# MeasurementCircuit.net
KiCad netlist of a schematic drawn in Altium Designer
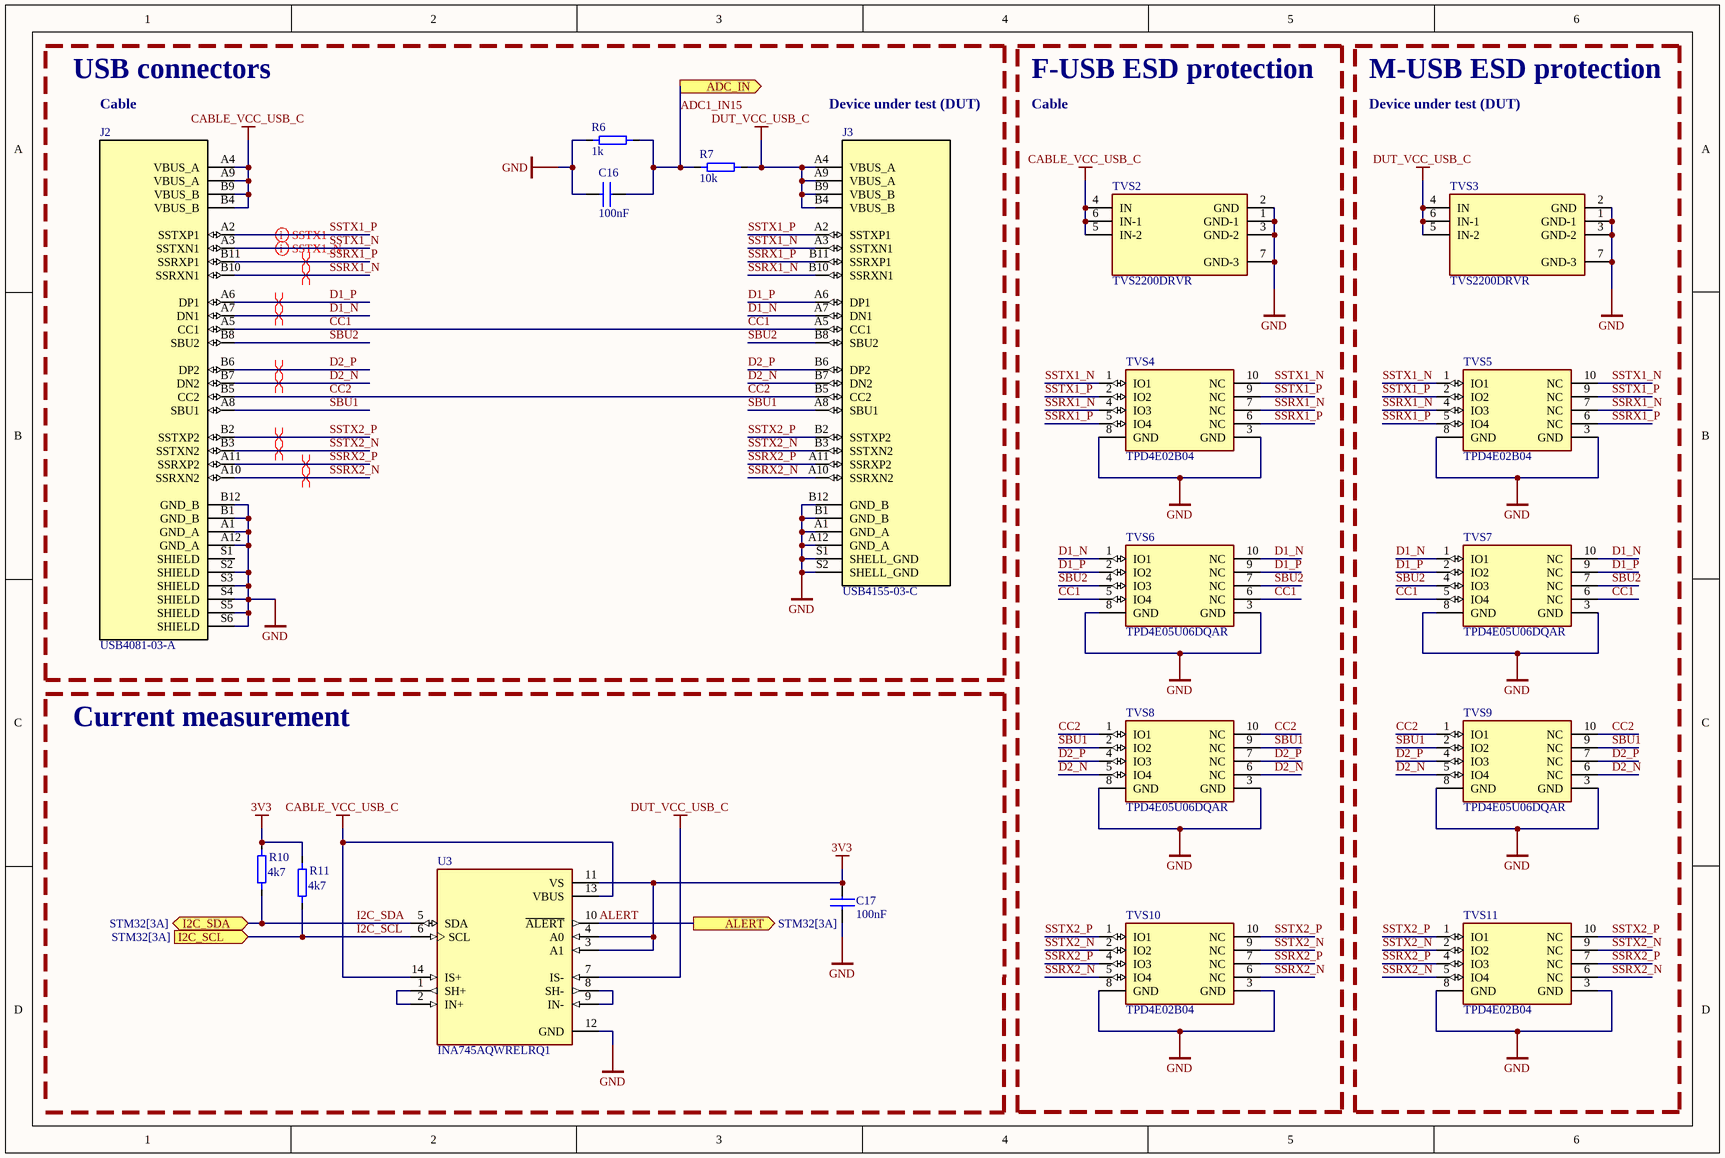
[diagram p0: MeasurementCircuit.SchDoc]

(export (version "E")
  (design (tool "Eeschema 10.0.6"))
  (components
    (comp (ref "C16")
      (value "100nF")
      (footprint "C0402")
      (description "Kondensator ceramiczny SMD")
      (libsource (lib "n16_discrete") (part "C"))
    )
    (comp (ref "C17")
      (value "100nF")
      (footprint "C0402")
      (description "Kondensator ceramiczny SMD")
      (libsource (lib "n16_discrete") (part "C"))
    )
    (comp (ref "J2")
      (value "USB4081-03-A")
      (footprint "USB4081-03-A")
      (description "Type C USB 3.2 Gen 2 Connector")
      (libsource (lib "USB_connectors") (part "USB4081-03-A"))
    )
    (comp (ref "J3")
      (value "USB4155-03-C")
      (footprint "USB4155-03-C")
      (libsource (lib "USB_connectors") (part "USB4155-03-C"))
    )
    (comp (ref "R6")
      (value "1k")
      (footprint "R0402")
      (description "Rezystor SMD")
      (libsource (lib "n16_discrete") (part "R"))
    )
    (comp (ref "R7")
      (value "10k")
      (footprint "R0603")
      (description "Rezystor SMD")
      (libsource (lib "n16_discrete") (part "R"))
    )
    (comp (ref "R10")
      (value "4k7")
      (footprint "R0402")
      (description "Rezystor SMD")
      (libsource (lib "n16_discrete") (part "R"))
    )
    (comp (ref "R11")
      (value "4k7")
      (footprint "R0402")
      (description "Rezystor SMD")
      (libsource (lib "n16_discrete") (part "R"))
    )
    (comp (ref "TVS2")
      (value "TVS2200DRVR")
      (footprint "TVS2200DRVR")
      (description "22V flat-clamp surge protection device")
      (libsource (lib "ESD_Protection") (part "TVS2200DRVR"))
    )
    (comp (ref "TVS3")
      (value "TVS2200DRVR")
      (footprint "TVS2200DRVR")
      (description "22V flat-clamp surge protection device")
      (libsource (lib "ESD_Protection") (part "TVS2200DRVR"))
    )
    (comp (ref "TVS4")
      (value "TPD4E02B04")
      (footprint "TPD4E02B04")
      (libsource (lib "ESD_Protection") (part "TPD4E02B04"))
    )
    (comp (ref "TVS5")
      (value "TPD4E02B04")
      (footprint "TPD4E02B04")
      (libsource (lib "ESD_Protection") (part "TPD4E02B04"))
    )
    (comp (ref "TVS6")
      (value "TPD4E05U06DQAR")
      (footprint "TPD4E05U06DQAR")
      (description "ESD Protection Diodes / TVS Diodes 0.66-pF +/-3.6-V +/- 30-kV ESD protectio")
      (libsource (lib "ESD_Protection") (part "TPD4E05U06DQAR"))
    )
    (comp (ref "TVS7")
      (value "TPD4E05U06DQAR")
      (footprint "TPD4E05U06DQAR")
      (description "ESD Protection Diodes / TVS Diodes 0.66-pF +/-3.6-V +/- 30-kV ESD protectio")
      (libsource (lib "ESD_Protection") (part "TPD4E05U06DQAR"))
    )
    (comp (ref "TVS8")
      (value "TPD4E05U06DQAR")
      (footprint "TPD4E05U06DQAR")
      (description "ESD Protection Diodes / TVS Diodes 0.66-pF +/-3.6-V +/- 30-kV ESD protectio")
      (libsource (lib "ESD_Protection") (part "TPD4E05U06DQAR"))
    )
    (comp (ref "TVS9")
      (value "TPD4E05U06DQAR")
      (footprint "TPD4E05U06DQAR")
      (description "ESD Protection Diodes / TVS Diodes 0.66-pF +/-3.6-V +/- 30-kV ESD protectio")
      (libsource (lib "ESD_Protection") (part "TPD4E05U06DQAR"))
    )
    (comp (ref "TVS10")
      (value "TPD4E02B04")
      (footprint "TPD4E02B04")
      (libsource (lib "ESD_Protection") (part "TPD4E02B04"))
    )
    (comp (ref "TVS11")
      (value "TPD4E02B04")
      (footprint "TPD4E02B04")
      (libsource (lib "ESD_Protection") (part "TPD4E02B04"))
    )
    (comp (ref "U3")
      (value "INA745AQWRELRQ1")
      (footprint "INA745AQWRELRQ1")
      (libsource (lib "ICs") (part "INA745AQWRELRQ1"))
    )
  )
  (nets
    (net (code "1") (name "/ADC1_IN15") (class "Default")
      (node (ref "C16") (pin "1") (pinfunction "1_1") (pintype "passive"))
      (node (ref "R6") (pin "2") (pinfunction "2_2") (pintype "passive"))
      (node (ref "R7") (pin "1") (pinfunction "1_1") (pintype "passive"))
    )
    (net (code "2") (name "/ALERT") (class "Default")
      (node (ref "U3") (pin "10") (pinfunction "~{ALERT}_10") (pintype "output"))
    )
    (net (code "3") (name "/CC1") (class "Default")
      (node (ref "J2") (pin "A5") (pinfunction "CC1_A5") (pintype "bidirectional"))
      (node (ref "J3") (pin "A5") (pinfunction "CC1_A5") (pintype "bidirectional"))
      (node (ref "TVS6") (pin "5") (pinfunction "IO4_5") (pintype "bidirectional"))
      (node (ref "TVS6") (pin "6") (pinfunction "NC_6") (pintype "passive"))
      (node (ref "TVS7") (pin "5") (pinfunction "IO4_5") (pintype "bidirectional"))
      (node (ref "TVS7") (pin "6") (pinfunction "NC_6") (pintype "passive"))
    )
    (net (code "4") (name "/CC2") (class "Default")
      (node (ref "J2") (pin "B5") (pinfunction "CC2_B5") (pintype "bidirectional"))
      (node (ref "J3") (pin "B5") (pinfunction "CC2_B5") (pintype "bidirectional"))
      (node (ref "TVS8") (pin "1") (pinfunction "IO1_1") (pintype "bidirectional"))
      (node (ref "TVS8") (pin "10") (pinfunction "NC_10") (pintype "passive"))
      (node (ref "TVS9") (pin "1") (pinfunction "IO1_1") (pintype "bidirectional"))
      (node (ref "TVS9") (pin "10") (pinfunction "NC_10") (pintype "passive"))
    )
    (net (code "5") (name "/D1_N") (class "Default")
      (node (ref "J2") (pin "A7") (pinfunction "DN1_A7") (pintype "bidirectional"))
      (node (ref "J3") (pin "A7") (pinfunction "DN1_A7") (pintype "bidirectional"))
      (node (ref "TVS6") (pin "1") (pinfunction "IO1_1") (pintype "bidirectional"))
      (node (ref "TVS6") (pin "10") (pinfunction "NC_10") (pintype "passive"))
      (node (ref "TVS7") (pin "1") (pinfunction "IO1_1") (pintype "bidirectional"))
      (node (ref "TVS7") (pin "10") (pinfunction "NC_10") (pintype "passive"))
    )
    (net (code "6") (name "/D1_P") (class "Default")
      (node (ref "J2") (pin "A6") (pinfunction "DP1_A6") (pintype "bidirectional"))
      (node (ref "J3") (pin "A6") (pinfunction "DP1_A6") (pintype "bidirectional"))
      (node (ref "TVS6") (pin "2") (pinfunction "IO2_2") (pintype "bidirectional"))
      (node (ref "TVS6") (pin "9") (pinfunction "NC_9") (pintype "passive"))
      (node (ref "TVS7") (pin "2") (pinfunction "IO2_2") (pintype "bidirectional"))
      (node (ref "TVS7") (pin "9") (pinfunction "NC_9") (pintype "passive"))
    )
    (net (code "7") (name "/D2_N") (class "Default")
      (node (ref "J2") (pin "B7") (pinfunction "DN2_B7") (pintype "bidirectional"))
      (node (ref "J3") (pin "B7") (pinfunction "DN2_B7") (pintype "bidirectional"))
      (node (ref "TVS8") (pin "5") (pinfunction "IO4_5") (pintype "bidirectional"))
      (node (ref "TVS8") (pin "6") (pinfunction "NC_6") (pintype "passive"))
      (node (ref "TVS9") (pin "5") (pinfunction "IO4_5") (pintype "bidirectional"))
      (node (ref "TVS9") (pin "6") (pinfunction "NC_6") (pintype "passive"))
    )
    (net (code "8") (name "/D2_P") (class "Default")
      (node (ref "J2") (pin "B6") (pinfunction "DP2_B6") (pintype "bidirectional"))
      (node (ref "J3") (pin "B6") (pinfunction "DP2_B6") (pintype "bidirectional"))
      (node (ref "TVS8") (pin "4") (pinfunction "IO3_4") (pintype "bidirectional"))
      (node (ref "TVS8") (pin "7") (pinfunction "NC_7") (pintype "passive"))
      (node (ref "TVS9") (pin "4") (pinfunction "IO3_4") (pintype "bidirectional"))
      (node (ref "TVS9") (pin "7") (pinfunction "NC_7") (pintype "passive"))
    )
    (net (code "9") (name "/I2C_SCL") (class "Default")
      (node (ref "R11") (pin "2") (pinfunction "2_2") (pintype "passive"))
      (node (ref "U3") (pin "6") (pinfunction "SCL_6") (pintype "input"))
    )
    (net (code "10") (name "/I2C_SDA") (class "Default")
      (node (ref "R10") (pin "2") (pinfunction "2_2") (pintype "passive"))
      (node (ref "U3") (pin "5") (pinfunction "SDA_5") (pintype "bidirectional"))
    )
    (net (code "11") (name "/SBU1") (class "Default")
      (node (ref "J2") (pin "A8") (pinfunction "SBU1_A8") (pintype "bidirectional"))
      (node (ref "J3") (pin "A8") (pinfunction "SBU1_A8") (pintype "bidirectional"))
      (node (ref "TVS8") (pin "2") (pinfunction "IO2_2") (pintype "bidirectional"))
      (node (ref "TVS8") (pin "9") (pinfunction "NC_9") (pintype "passive"))
      (node (ref "TVS9") (pin "2") (pinfunction "IO2_2") (pintype "bidirectional"))
      (node (ref "TVS9") (pin "9") (pinfunction "NC_9") (pintype "passive"))
    )
    (net (code "12") (name "/SBU2") (class "Default")
      (node (ref "J2") (pin "B8") (pinfunction "SBU2_B8") (pintype "bidirectional"))
      (node (ref "J3") (pin "B8") (pinfunction "SBU2_B8") (pintype "bidirectional"))
      (node (ref "TVS6") (pin "4") (pinfunction "IO3_4") (pintype "bidirectional"))
      (node (ref "TVS6") (pin "7") (pinfunction "NC_7") (pintype "passive"))
      (node (ref "TVS7") (pin "4") (pinfunction "IO3_4") (pintype "bidirectional"))
      (node (ref "TVS7") (pin "7") (pinfunction "NC_7") (pintype "passive"))
    )
    (net (code "13") (name "/SSRX1_N") (class "Default")
      (node (ref "J2") (pin "B10") (pinfunction "SSRXN1_B10") (pintype "bidirectional"))
      (node (ref "J3") (pin "B10") (pinfunction "SSRXN1_B10") (pintype "bidirectional"))
      (node (ref "TVS4") (pin "4") (pinfunction "IO3_4") (pintype "bidirectional"))
      (node (ref "TVS4") (pin "7") (pinfunction "NC_7") (pintype "passive"))
      (node (ref "TVS5") (pin "4") (pinfunction "IO3_4") (pintype "bidirectional"))
      (node (ref "TVS5") (pin "7") (pinfunction "NC_7") (pintype "passive"))
    )
    (net (code "14") (name "/SSRX1_P") (class "Default")
      (node (ref "J2") (pin "B11") (pinfunction "SSRXP1_B11") (pintype "bidirectional"))
      (node (ref "J3") (pin "B11") (pinfunction "SSRXP1_B11") (pintype "bidirectional"))
      (node (ref "TVS4") (pin "5") (pinfunction "IO4_5") (pintype "bidirectional"))
      (node (ref "TVS4") (pin "6") (pinfunction "NC_6") (pintype "passive"))
      (node (ref "TVS5") (pin "5") (pinfunction "IO4_5") (pintype "bidirectional"))
      (node (ref "TVS5") (pin "6") (pinfunction "NC_6") (pintype "passive"))
    )
    (net (code "15") (name "/SSRX2_N") (class "Default")
      (node (ref "J2") (pin "A10") (pinfunction "SSRXN2_A10") (pintype "bidirectional"))
      (node (ref "J3") (pin "A10") (pinfunction "SSRXN2_A10") (pintype "bidirectional"))
      (node (ref "TVS10") (pin "5") (pinfunction "IO4_5") (pintype "bidirectional"))
      (node (ref "TVS10") (pin "6") (pinfunction "NC_6") (pintype "passive"))
      (node (ref "TVS11") (pin "5") (pinfunction "IO4_5") (pintype "bidirectional"))
      (node (ref "TVS11") (pin "6") (pinfunction "NC_6") (pintype "passive"))
    )
    (net (code "16") (name "/SSRX2_P") (class "Default")
      (node (ref "J2") (pin "A11") (pinfunction "SSRXP2_A11") (pintype "bidirectional"))
      (node (ref "J3") (pin "A11") (pinfunction "SSRXP2_A11") (pintype "bidirectional"))
      (node (ref "TVS10") (pin "4") (pinfunction "IO3_4") (pintype "bidirectional"))
      (node (ref "TVS10") (pin "7") (pinfunction "NC_7") (pintype "passive"))
      (node (ref "TVS11") (pin "4") (pinfunction "IO3_4") (pintype "bidirectional"))
      (node (ref "TVS11") (pin "7") (pinfunction "NC_7") (pintype "passive"))
    )
    (net (code "17") (name "/SSTX1_N") (class "Default")
      (node (ref "J2") (pin "A3") (pinfunction "SSTXN1_A3") (pintype "bidirectional"))
      (node (ref "J3") (pin "A3") (pinfunction "SSTXN1_A3") (pintype "bidirectional"))
      (node (ref "TVS4") (pin "1") (pinfunction "IO1_1") (pintype "bidirectional"))
      (node (ref "TVS4") (pin "10") (pinfunction "NC_10") (pintype "passive"))
      (node (ref "TVS5") (pin "1") (pinfunction "IO1_1") (pintype "bidirectional"))
      (node (ref "TVS5") (pin "10") (pinfunction "NC_10") (pintype "passive"))
    )
    (net (code "18") (name "/SSTX1_P") (class "Default")
      (node (ref "J2") (pin "A2") (pinfunction "SSTXP1_A2") (pintype "bidirectional"))
      (node (ref "J3") (pin "A2") (pinfunction "SSTXP1_A2") (pintype "bidirectional"))
      (node (ref "TVS4") (pin "2") (pinfunction "IO2_2") (pintype "bidirectional"))
      (node (ref "TVS4") (pin "9") (pinfunction "NC_9") (pintype "passive"))
      (node (ref "TVS5") (pin "2") (pinfunction "IO2_2") (pintype "bidirectional"))
      (node (ref "TVS5") (pin "9") (pinfunction "NC_9") (pintype "passive"))
    )
    (net (code "19") (name "/SSTX2_N") (class "Default")
      (node (ref "J2") (pin "B3") (pinfunction "SSTXN2_B3") (pintype "bidirectional"))
      (node (ref "J3") (pin "B3") (pinfunction "SSTXN2_B3") (pintype "bidirectional"))
      (node (ref "TVS10") (pin "2") (pinfunction "IO2_2") (pintype "bidirectional"))
      (node (ref "TVS10") (pin "9") (pinfunction "NC_9") (pintype "passive"))
      (node (ref "TVS11") (pin "2") (pinfunction "IO2_2") (pintype "bidirectional"))
      (node (ref "TVS11") (pin "9") (pinfunction "NC_9") (pintype "passive"))
    )
    (net (code "20") (name "/SSTX2_P") (class "Default")
      (node (ref "J2") (pin "B2") (pinfunction "SSTXP2_B2") (pintype "bidirectional"))
      (node (ref "J3") (pin "B2") (pinfunction "SSTXP2_B2") (pintype "bidirectional"))
      (node (ref "TVS10") (pin "1") (pinfunction "IO1_1") (pintype "bidirectional"))
      (node (ref "TVS10") (pin "10") (pinfunction "NC_10") (pintype "passive"))
      (node (ref "TVS11") (pin "1") (pinfunction "IO1_1") (pintype "bidirectional"))
      (node (ref "TVS11") (pin "10") (pinfunction "NC_10") (pintype "passive"))
    )
    (net (code "21") (name "3V3") (class "Default")
      (node (ref "C17") (pin "1") (pinfunction "1_1") (pintype "passive"))
      (node (ref "R10") (pin "1") (pinfunction "1_1") (pintype "passive"))
      (node (ref "R11") (pin "1") (pinfunction "1_1") (pintype "passive"))
      (node (ref "U3") (pin "11") (pinfunction "VS_11") (pintype "power_in"))
      (node (ref "U3") (pin "3") (pinfunction "A1_3") (pintype "input"))
      (node (ref "U3") (pin "4") (pinfunction "A0_4") (pintype "input"))
    )
    (net (code "22") (name "CABLE_VCC_USB_C") (class "Default")
      (node (ref "J2") (pin "A4") (pinfunction "VBUS_A_A4") (pintype "power_in"))
      (node (ref "J2") (pin "A9") (pinfunction "VBUS_A_A9") (pintype "power_in"))
      (node (ref "J2") (pin "B4") (pinfunction "VBUS_B_B4") (pintype "power_in"))
      (node (ref "J2") (pin "B9") (pinfunction "VBUS_B_B9") (pintype "power_in"))
      (node (ref "TVS2") (pin "4") (pinfunction "IN_4") (pintype "power_in"))
      (node (ref "TVS2") (pin "5") (pinfunction "IN-2_5") (pintype "power_in"))
      (node (ref "TVS2") (pin "6") (pinfunction "IN-1_6") (pintype "power_in"))
      (node (ref "U3") (pin "13") (pinfunction "VBUS_13") (pintype "power_in"))
      (node (ref "U3") (pin "14") (pinfunction "IS+_14") (pintype "input"))
    )
    (net (code "23") (name "DUT_VCC_USB_C") (class "Default")
      (node (ref "J3") (pin "A4") (pinfunction "VBUS_A_A4") (pintype "power_in"))
      (node (ref "J3") (pin "A9") (pinfunction "VBUS_A_A9") (pintype "power_in"))
      (node (ref "J3") (pin "B4") (pinfunction "VBUS_B_B4") (pintype "power_in"))
      (node (ref "J3") (pin "B9") (pinfunction "VBUS_B_B9") (pintype "power_in"))
      (node (ref "R7") (pin "2") (pinfunction "2_2") (pintype "passive"))
      (node (ref "TVS3") (pin "4") (pinfunction "IN_4") (pintype "power_in"))
      (node (ref "TVS3") (pin "5") (pinfunction "IN-2_5") (pintype "power_in"))
      (node (ref "TVS3") (pin "6") (pinfunction "IN-1_6") (pintype "power_in"))
      (node (ref "U3") (pin "7") (pinfunction "IS-_7") (pintype "input"))
    )
    (net (code "24") (name "GND") (class "Default")
      (node (ref "C16") (pin "2") (pinfunction "2_2") (pintype "passive"))
      (node (ref "C17") (pin "2") (pinfunction "2_2") (pintype "passive"))
      (node (ref "J2") (pin "A1") (pinfunction "GND_A_A1") (pintype "power_in"))
      (node (ref "J2") (pin "A12") (pinfunction "GND_A_A12") (pintype "power_in"))
      (node (ref "J2") (pin "B1") (pinfunction "GND_B_B1") (pintype "power_in"))
      (node (ref "J2") (pin "B12") (pinfunction "GND_B_B12") (pintype "power_in"))
      (node (ref "J2") (pin "S2") (pinfunction "SHIELD_S2") (pintype "power_in"))
      (node (ref "J2") (pin "S3") (pinfunction "SHIELD_S3") (pintype "passive"))
      (node (ref "J2") (pin "S4") (pinfunction "SHIELD_S4") (pintype "passive"))
      (node (ref "J2") (pin "S5") (pinfunction "SHIELD_S5") (pintype "passive"))
      (node (ref "J2") (pin "S6") (pinfunction "SHIELD_S6") (pintype "passive"))
      (node (ref "J3") (pin "A1") (pinfunction "GND_A_A1") (pintype "power_in"))
      (node (ref "J3") (pin "A12") (pinfunction "GND_A_A12") (pintype "power_in"))
      (node (ref "J3") (pin "B1") (pinfunction "GND_B_B1") (pintype "power_in"))
      (node (ref "J3") (pin "B12") (pinfunction "GND_B_B12") (pintype "power_in"))
      (node (ref "J3") (pin "S1") (pinfunction "SHELL_GND_S1") (pintype "power_in"))
      (node (ref "J3") (pin "S2") (pinfunction "SHELL_GND_S2") (pintype "power_in"))
      (node (ref "R6") (pin "1") (pinfunction "1_1") (pintype "passive"))
      (node (ref "TVS10") (pin "3") (pinfunction "GND_3") (pintype "power_in"))
      (node (ref "TVS10") (pin "8") (pinfunction "GND_8") (pintype "power_in"))
      (node (ref "TVS11") (pin "3") (pinfunction "GND_3") (pintype "power_in"))
      (node (ref "TVS11") (pin "8") (pinfunction "GND_8") (pintype "power_in"))
      (node (ref "TVS2") (pin "1") (pinfunction "GND-1_1") (pintype "power_in"))
      (node (ref "TVS2") (pin "2") (pinfunction "GND_2") (pintype "power_in"))
      (node (ref "TVS2") (pin "3") (pinfunction "GND-2_3") (pintype "power_in"))
      (node (ref "TVS2") (pin "7") (pinfunction "GND-3_7") (pintype "power_in"))
      (node (ref "TVS3") (pin "1") (pinfunction "GND-1_1") (pintype "power_in"))
      (node (ref "TVS3") (pin "2") (pinfunction "GND_2") (pintype "power_in"))
      (node (ref "TVS3") (pin "3") (pinfunction "GND-2_3") (pintype "power_in"))
      (node (ref "TVS3") (pin "7") (pinfunction "GND-3_7") (pintype "power_in"))
      (node (ref "TVS4") (pin "3") (pinfunction "GND_3") (pintype "power_in"))
      (node (ref "TVS4") (pin "8") (pinfunction "GND_8") (pintype "power_in"))
      (node (ref "TVS5") (pin "3") (pinfunction "GND_3") (pintype "power_in"))
      (node (ref "TVS5") (pin "8") (pinfunction "GND_8") (pintype "power_in"))
      (node (ref "TVS6") (pin "3") (pinfunction "GND_3") (pintype "power_in"))
      (node (ref "TVS6") (pin "8") (pinfunction "GND_8") (pintype "power_in"))
      (node (ref "TVS7") (pin "3") (pinfunction "GND_3") (pintype "power_in"))
      (node (ref "TVS7") (pin "8") (pinfunction "GND_8") (pintype "power_in"))
      (node (ref "TVS8") (pin "3") (pinfunction "GND_3") (pintype "power_in"))
      (node (ref "TVS8") (pin "8") (pinfunction "GND_8") (pintype "power_in"))
      (node (ref "TVS9") (pin "3") (pinfunction "GND_3") (pintype "power_in"))
      (node (ref "TVS9") (pin "8") (pinfunction "GND_8") (pintype "power_in"))
      (node (ref "U3") (pin "12") (pinfunction "GND_12") (pintype "power_in"))
    )
    (net (code "25") (name "Net-(U3-IN+)") (class "Default")
      (node (ref "U3") (pin "1") (pinfunction "SH+_1") (pintype "output"))
      (node (ref "U3") (pin "2") (pinfunction "IN+_2") (pintype "input"))
    )
    (net (code "26") (name "Net-(U3-IN-)") (class "Default")
      (node (ref "U3") (pin "8") (pinfunction "SH-_8") (pintype "output"))
      (node (ref "U3") (pin "9") (pinfunction "IN-_9") (pintype "input"))
    )
    (net (code "27") (name "unconnected-(J2-SHIELD-PadS1)") (class "Default")
      (node (ref "J2") (pin "S1") (pinfunction "SHIELD_S1") (pintype "power_in"))
    )
  )
)
